# untitled.net
KiCad netlist of a schematic drawn in EAGLE
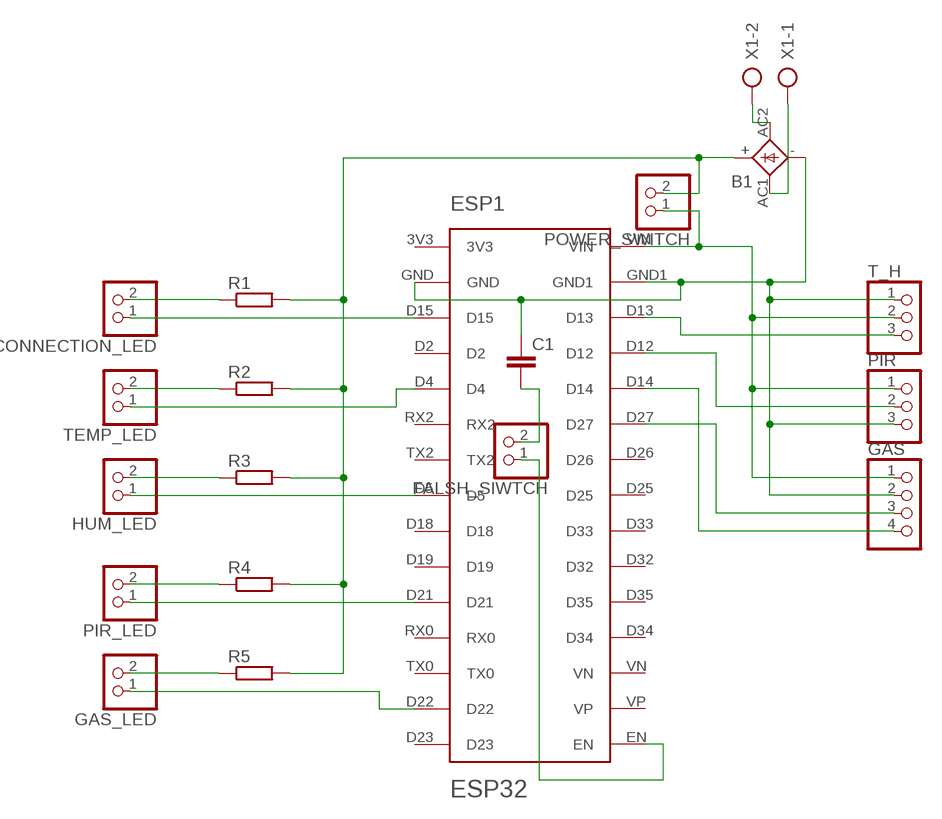
[diagram p0: schematic, sheet 1]

(export (version "E")
  (design (tool "Eeschema 10.0.6"))
  (components
    (comp (ref "B1")
      (value "2KBB-R")
      (footprint "eagle-import:2KBB-R")
      (libsource (lib "eagle-import") (part "2KBB-R"))
    )
    (comp (ref "C1")
      (value "C5/2.5")
      (footprint "eagle-import:C5B2.5")
      (libsource (lib "eagle-import") (part "C5/2.5"))
    )
    (comp (ref "CONNECTION_LED")
      (value "PINHD-1X2")
      (footprint "eagle-import:1X02")
      (libsource (lib "eagle-import") (part "PINHD-1X2"))
    )
    (comp (ref "ESP1")
      (value "ESP32")
      (footprint "eagle-import:ESP-32")
      (libsource (lib "eagle-import") (part "ESP32"))
    )
    (comp (ref "FALSH_SIWTCH")
      (value "PINHD-1X2")
      (footprint "eagle-import:1X02")
      (libsource (lib "eagle-import") (part "PINHD-1X2"))
    )
    (comp (ref "GAS")
      (value "PINHD-1X4")
      (footprint "eagle-import:1X04")
      (libsource (lib "eagle-import") (part "PINHD-1X4"))
    )
    (comp (ref "GAS_LED")
      (value "PINHD-1X2")
      (footprint "eagle-import:1X02")
      (libsource (lib "eagle-import") (part "PINHD-1X2"))
    )
    (comp (ref "HUM_LED")
      (value "PINHD-1X2")
      (footprint "eagle-import:1X02")
      (libsource (lib "eagle-import") (part "PINHD-1X2"))
    )
    (comp (ref "PIR")
      (value "PINHD-1X3")
      (footprint "eagle-import:1X03")
      (libsource (lib "eagle-import") (part "PINHD-1X3"))
    )
    (comp (ref "PIR_LED")
      (value "PINHD-1X2")
      (footprint "eagle-import:1X02")
      (libsource (lib "eagle-import") (part "PINHD-1X2"))
    )
    (comp (ref "POWER_SWITCH")
      (value "PINHD-1X2")
      (footprint "eagle-import:1X02")
      (libsource (lib "eagle-import") (part "PINHD-1X2"))
    )
    (comp (ref "R1")
      (value "R-EU_0207/10")
      (footprint "eagle-import:0207_10")
      (libsource (lib "eagle-import") (part "R-EU_0207/10"))
    )
    (comp (ref "R2")
      (value "R-EU_0207/10")
      (footprint "eagle-import:0207_10")
      (libsource (lib "eagle-import") (part "R-EU_0207/10"))
    )
    (comp (ref "R3")
      (value "R-EU_0207/10")
      (footprint "eagle-import:0207_10")
      (libsource (lib "eagle-import") (part "R-EU_0207/10"))
    )
    (comp (ref "R4")
      (value "R-EU_0207/10")
      (footprint "eagle-import:0207_10")
      (libsource (lib "eagle-import") (part "R-EU_0207/10"))
    )
    (comp (ref "R5")
      (value "R-EU_0207/10")
      (footprint "eagle-import:0207_10")
      (libsource (lib "eagle-import") (part "R-EU_0207/10"))
    )
    (comp (ref "TEMP_LED")
      (value "PINHD-1X2")
      (footprint "eagle-import:1X02")
      (libsource (lib "eagle-import") (part "PINHD-1X2"))
    )
    (comp (ref "T_H")
      (value "PINHD-1X3")
      (footprint "eagle-import:1X03")
      (libsource (lib "eagle-import") (part "PINHD-1X3"))
    )
    (comp (ref "X1")
      (value "AK300/2")
      (footprint "eagle-import:AK300_2")
      (libsource (lib "eagle-import") (part "AK300/2"))
    )
  )
  (nets
    (net (code "1") (name "Net-(B1-Pad+)") (class "Default")
      (node (ref "B1") (pin "+") (pinfunction "+_+") (pintype "passive"))
      (node (ref "POWER_SWITCH") (pin "2") (pinfunction "2_2") (pintype "passive"))
      (node (ref "R1") (pin "2") (pinfunction "2_2") (pintype "passive"))
      (node (ref "R2") (pin "2") (pinfunction "2_2") (pintype "passive"))
      (node (ref "R3") (pin "2") (pinfunction "2_2") (pintype "passive"))
      (node (ref "R4") (pin "2") (pinfunction "2_2") (pintype "passive"))
      (node (ref "R5") (pin "2") (pinfunction "2_2") (pintype "passive"))
    )
    (net (code "2") (name "Net-(B1-Pad-)") (class "Default")
      (node (ref "B1") (pin "-") (pinfunction "-_-") (pintype "passive"))
      (node (ref "C1") (pin "1") (pinfunction "1_1") (pintype "passive"))
      (node (ref "ESP1") (pin "GND") (pinfunction "GND_GND") (pintype "bidirectional"))
      (node (ref "ESP1") (pin "GND1") (pinfunction "GND1_GND1") (pintype "bidirectional"))
      (node (ref "GAS") (pin "2") (pinfunction "2_2") (pintype "passive"))
      (node (ref "PIR") (pin "3") (pinfunction "3_3") (pintype "passive"))
      (node (ref "T_H") (pin "1") (pinfunction "1_1") (pintype "passive"))
    )
    (net (code "3") (name "Net-(C1-Pad2)") (class "Default")
      (node (ref "C1") (pin "2") (pinfunction "2_2") (pintype "passive"))
      (node (ref "FALSH_SIWTCH") (pin "2") (pinfunction "2_2") (pintype "passive"))
    )
    (net (code "4") (name "Net-(CONNECTION_LED-Pad1)") (class "Default")
      (node (ref "CONNECTION_LED") (pin "1") (pinfunction "1_1") (pintype "passive"))
      (node (ref "ESP1") (pin "D15") (pinfunction "D15_D15") (pintype "bidirectional"))
    )
    (net (code "5") (name "Net-(CONNECTION_LED-Pad2)") (class "Default")
      (node (ref "CONNECTION_LED") (pin "2") (pinfunction "2_2") (pintype "passive"))
      (node (ref "R1") (pin "1") (pinfunction "1_1") (pintype "passive"))
    )
    (net (code "6") (name "Net-(ESP1-PadD4)") (class "Default")
      (node (ref "ESP1") (pin "D4") (pinfunction "D4_D4") (pintype "bidirectional"))
      (node (ref "TEMP_LED") (pin "1") (pinfunction "1_1") (pintype "passive"))
    )
    (net (code "7") (name "Net-(ESP1-PadD5)") (class "Default")
      (node (ref "ESP1") (pin "D5") (pinfunction "D5_D5") (pintype "bidirectional"))
      (node (ref "HUM_LED") (pin "1") (pinfunction "1_1") (pintype "passive"))
    )
    (net (code "8") (name "Net-(ESP1-PadD12)") (class "Default")
      (node (ref "ESP1") (pin "D12") (pinfunction "D12_D12") (pintype "bidirectional"))
      (node (ref "PIR") (pin "2") (pinfunction "2_2") (pintype "passive"))
    )
    (net (code "9") (name "Net-(ESP1-PadD13)") (class "Default")
      (node (ref "ESP1") (pin "D13") (pinfunction "D13_D13") (pintype "bidirectional"))
      (node (ref "T_H") (pin "3") (pinfunction "3_3") (pintype "passive"))
    )
    (net (code "10") (name "Net-(ESP1-PadD14)") (class "Default")
      (node (ref "ESP1") (pin "D14") (pinfunction "D14_D14") (pintype "bidirectional"))
      (node (ref "GAS") (pin "4") (pinfunction "4_4") (pintype "passive"))
    )
    (net (code "11") (name "Net-(ESP1-PadD21)") (class "Default")
      (node (ref "ESP1") (pin "D21") (pinfunction "D21_D21") (pintype "bidirectional"))
      (node (ref "PIR_LED") (pin "1") (pinfunction "1_1") (pintype "passive"))
    )
    (net (code "12") (name "Net-(ESP1-PadD22)") (class "Default")
      (node (ref "ESP1") (pin "D22") (pinfunction "D22_D22") (pintype "bidirectional"))
      (node (ref "GAS_LED") (pin "1") (pinfunction "1_1") (pintype "passive"))
    )
    (net (code "13") (name "Net-(ESP1-PadD27)") (class "Default")
      (node (ref "ESP1") (pin "D27") (pinfunction "D27_D27") (pintype "bidirectional"))
      (node (ref "GAS") (pin "3") (pinfunction "3_3") (pintype "passive"))
    )
    (net (code "14") (name "Net-(ESP1-PadEN)") (class "Default")
      (node (ref "ESP1") (pin "EN") (pinfunction "EN_EN") (pintype "bidirectional"))
      (node (ref "FALSH_SIWTCH") (pin "1") (pinfunction "1_1") (pintype "passive"))
    )
    (net (code "15") (name "Net-(ESP1-PadVIN)") (class "Default")
      (node (ref "ESP1") (pin "VIN") (pinfunction "VIN_VIN") (pintype "bidirectional"))
      (node (ref "GAS") (pin "1") (pinfunction "1_1") (pintype "passive"))
      (node (ref "PIR") (pin "1") (pinfunction "1_1") (pintype "passive"))
      (node (ref "POWER_SWITCH") (pin "1") (pinfunction "1_1") (pintype "passive"))
      (node (ref "T_H") (pin "2") (pinfunction "2_2") (pintype "passive"))
    )
    (net (code "16") (name "Net-(GAS_LED-Pad2)") (class "Default")
      (node (ref "GAS_LED") (pin "2") (pinfunction "2_2") (pintype "passive"))
      (node (ref "R5") (pin "1") (pinfunction "1_1") (pintype "passive"))
    )
    (net (code "17") (name "Net-(HUM_LED-Pad2)") (class "Default")
      (node (ref "HUM_LED") (pin "2") (pinfunction "2_2") (pintype "passive"))
      (node (ref "R3") (pin "1") (pinfunction "1_1") (pintype "passive"))
    )
    (net (code "18") (name "Net-(PIR_LED-Pad2)") (class "Default")
      (node (ref "PIR_LED") (pin "2") (pinfunction "2_2") (pintype "passive"))
      (node (ref "R4") (pin "1") (pinfunction "1_1") (pintype "passive"))
    )
    (net (code "19") (name "Net-(R2-Pad1)") (class "Default")
      (node (ref "R2") (pin "1") (pinfunction "1_1") (pintype "passive"))
      (node (ref "TEMP_LED") (pin "2") (pinfunction "2_2") (pintype "passive"))
    )
    (net (code "20") (name "Net-(X1A-KL)") (class "Default")
      (node (ref "B1") (pin "AC1") (pinfunction "AC1_AC1") (pintype "passive"))
      (node (ref "X1") (pin "1") (pinfunction "KL_1") (pintype "passive"))
    )
    (net (code "21") (name "Net-(X1B-KL)") (class "Default")
      (node (ref "B1") (pin "AC2") (pinfunction "AC2_AC2") (pintype "passive"))
      (node (ref "X1") (pin "2") (pinfunction "KL_2") (pintype "passive"))
    )
    (net (code "22") (name "unconnected-(ESP1-Pad3V3)") (class "Default")
      (node (ref "ESP1") (pin "3V3") (pinfunction "3V3_3V3") (pintype "bidirectional"))
    )
    (net (code "23") (name "unconnected-(ESP1-PadD2)") (class "Default")
      (node (ref "ESP1") (pin "D2") (pinfunction "D2_D2") (pintype "bidirectional"))
    )
    (net (code "24") (name "unconnected-(ESP1-PadD18)") (class "Default")
      (node (ref "ESP1") (pin "D18") (pinfunction "D18_D18") (pintype "bidirectional"))
    )
    (net (code "25") (name "unconnected-(ESP1-PadD19)") (class "Default")
      (node (ref "ESP1") (pin "D19") (pinfunction "D19_D19") (pintype "bidirectional"))
    )
    (net (code "26") (name "unconnected-(ESP1-PadD23)") (class "Default")
      (node (ref "ESP1") (pin "D23") (pinfunction "D23_D23") (pintype "bidirectional"))
    )
    (net (code "27") (name "unconnected-(ESP1-PadD25)") (class "Default")
      (node (ref "ESP1") (pin "D25") (pinfunction "D25_D25") (pintype "bidirectional"))
    )
    (net (code "28") (name "unconnected-(ESP1-PadD26)") (class "Default")
      (node (ref "ESP1") (pin "D26") (pinfunction "D26_D26") (pintype "bidirectional"))
    )
    (net (code "29") (name "unconnected-(ESP1-PadD32)") (class "Default")
      (node (ref "ESP1") (pin "D32") (pinfunction "D32_D32") (pintype "bidirectional"))
    )
    (net (code "30") (name "unconnected-(ESP1-PadD33)") (class "Default")
      (node (ref "ESP1") (pin "D33") (pinfunction "D33_D33") (pintype "bidirectional"))
    )
    (net (code "31") (name "unconnected-(ESP1-PadD34)") (class "Default")
      (node (ref "ESP1") (pin "D34") (pinfunction "D34_D34") (pintype "bidirectional"))
    )
    (net (code "32") (name "unconnected-(ESP1-PadD35)") (class "Default")
      (node (ref "ESP1") (pin "D35") (pinfunction "D35_D35") (pintype "bidirectional"))
    )
    (net (code "33") (name "unconnected-(ESP1-PadRX0)") (class "Default")
      (node (ref "ESP1") (pin "RX0") (pinfunction "RX0_RX0") (pintype "bidirectional"))
    )
    (net (code "34") (name "unconnected-(ESP1-PadRX2)") (class "Default")
      (node (ref "ESP1") (pin "RX2") (pinfunction "RX2_RX2") (pintype "bidirectional"))
    )
    (net (code "35") (name "unconnected-(ESP1-PadTX0)") (class "Default")
      (node (ref "ESP1") (pin "TX0") (pinfunction "TX0_TX0") (pintype "bidirectional"))
    )
    (net (code "36") (name "unconnected-(ESP1-PadTX2)") (class "Default")
      (node (ref "ESP1") (pin "TX2") (pinfunction "TX2_TX2") (pintype "bidirectional"))
    )
    (net (code "37") (name "unconnected-(ESP1-PadVN)") (class "Default")
      (node (ref "ESP1") (pin "VN") (pinfunction "VN_VN") (pintype "bidirectional"))
    )
    (net (code "38") (name "unconnected-(ESP1-PadVP)") (class "Default")
      (node (ref "ESP1") (pin "VP") (pinfunction "VP_VP") (pintype "bidirectional"))
    )
  )
)
